# MR_UartConnector.net
KiCad netlist of a schematic drawn in Altium Designer
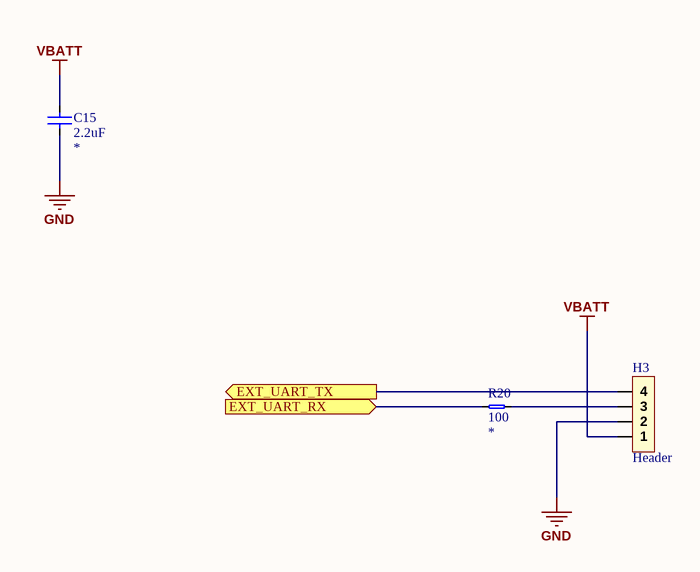
[diagram p0: MR_UartConnector.SchDoc]

(export (version "E")
  (design (tool "Eeschema 10.0.6"))
  (components
    (comp (ref "C15")
      (value "2.2uF")
      (footprint "0603_CAP_LD")
      (description "Ceramic Capacitor")
      (fields (field (name "PACKAGE") "*") (field (name "Comment") "CerCap"))
      (libsource (lib "MiniRobot") (part "CerCap"))
    )
    (comp (ref "H3")
      (value "Header")
      (footprint "HE14 1x4 Straight")
      (description "Header 4x1 PIns")
      (libsource (lib "MiniRobot") (part "Header_4x1"))
    )
    (comp (ref "R20")
      (value "100")
      (footprint "0603_RES_LD")
      (description "Resistor")
      (fields (field (name "PACKAGE") "*"))
      (libsource (lib "MiniRobot") (part "Resistor"))
    )
  )
  (nets
    (net (code "1") (name "/EXT_UART_RX") (class "Default")
      (node (ref "R20") (pin "1") (pinfunction "1_1") (pintype "passive"))
    )
    (net (code "2") (name "/EXT_UART_TX") (class "Default")
      (node (ref "H3") (pin "4") (pinfunction "4_4") (pintype "passive"))
    )
    (net (code "3") (name "GND") (class "Default")
      (node (ref "C15") (pin "1") (pinfunction "1_1") (pintype "passive"))
      (node (ref "H3") (pin "2") (pinfunction "2_2") (pintype "passive"))
    )
    (net (code "4") (name "Net-(H3-Pad3)") (class "Default")
      (node (ref "H3") (pin "3") (pinfunction "3_3") (pintype "passive"))
      (node (ref "R20") (pin "2") (pinfunction "2_2") (pintype "passive"))
    )
    (net (code "5") (name "VBATT") (class "Default")
      (node (ref "C15") (pin "2") (pinfunction "2_2") (pintype "passive"))
      (node (ref "H3") (pin "1") (pinfunction "1_1") (pintype "passive"))
    )
  )
)
